# SD_Card.net
KiCad netlist of a schematic drawn in Altium Designer
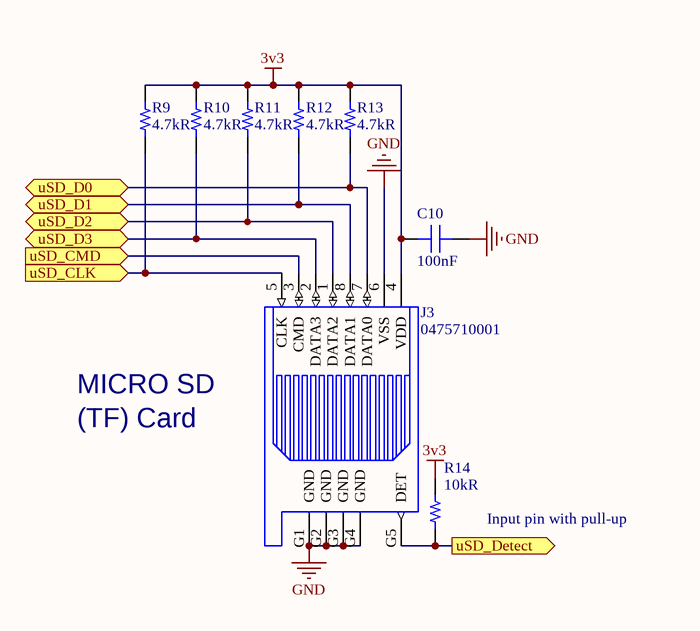
[diagram p0: SD Card.SchDoc]

(export (version "E")
  (design (tool "Eeschema 10.0.6"))
  (components
    (comp (ref "C10")
      (value "100nF")
      (footprint "CAP 0603/1608")
      (description "Ceramic, SMT Capacitor")
      (fields
        (field (name "MANUFACTURER") "Samsung")
        (field (name "MANUFACTURER PART NUMBER") "CL10B104JB8NNNC")
      )
      (libsource (lib "yildizIoT Library") (part "Capacitor - Ceramic"))
    )
    (comp (ref "J3")
      (value "0475710001")
      (footprint "Molex - 0475710001")
      (description "Connector")
      (fields (field (name "MANUFACTURER") "Molex"))
      (libsource (lib "yildizIoT Library") (part "uSD Card"))
    )
    (comp (ref "R9")
      (value "4.7kR")
      (footprint "RES 0603/1608")
      (description "Ceramic, SMT Capacitor")
      (fields
        (field (name "MANUFACTURER") "Yageo")
        (field (name "MANUFACTURER PART NUMBER") "RC0603JR-074K7L")
      )
      (libsource (lib "yildizIoT Library") (part "Resistor_Chip"))
    )
    (comp (ref "R10")
      (value "4.7kR")
      (footprint "RES 0603/1608")
      (description "Ceramic, SMT Capacitor")
      (fields
        (field (name "MANUFACTURER") "Yageo")
        (field (name "MANUFACTURER PART NUMBER") "RC0603JR-074K7L")
      )
      (libsource (lib "yildizIoT Library") (part "Resistor_Chip"))
    )
    (comp (ref "R11")
      (value "4.7kR")
      (footprint "RES 0603/1608")
      (description "Ceramic, SMT Capacitor")
      (fields
        (field (name "MANUFACTURER") "Yageo")
        (field (name "MANUFACTURER PART NUMBER") "RC0603JR-074K7L")
      )
      (libsource (lib "yildizIoT Library") (part "Resistor_Chip"))
    )
    (comp (ref "R12")
      (value "4.7kR")
      (footprint "RES 0603/1608")
      (description "Ceramic, SMT Capacitor")
      (fields
        (field (name "MANUFACTURER") "Yageo")
        (field (name "MANUFACTURER PART NUMBER") "RC0603JR-074K7L")
      )
      (libsource (lib "yildizIoT Library") (part "Resistor_Chip"))
    )
    (comp (ref "R13")
      (value "4.7kR")
      (footprint "RES 0603/1608")
      (description "Ceramic, SMT Capacitor")
      (fields
        (field (name "MANUFACTURER") "Yageo")
        (field (name "MANUFACTURER PART NUMBER") "RC0603JR-074K7L")
      )
      (libsource (lib "yildizIoT Library") (part "Resistor_Chip"))
    )
    (comp (ref "R14")
      (value "10kR")
      (footprint "RES 0603/1608")
      (description "Ceramic, SMT Capacitor")
      (fields
        (field (name "MANUFACTURER") "Stackpole Electronics")
        (field (name "MANUFACTURER PART NUMBER") "RNCP0603FTD10K0")
      )
      (libsource (lib "yildizIoT Library") (part "Resistor_Chip"))
    )
  )
  (nets
    (net (code "1") (name "/uSD_CLK") (class "Default")
      (node (ref "J3") (pin "5") (pinfunction "CLK_5") (pintype "input"))
      (node (ref "R9") (pin "1") (pinfunction "1_1") (pintype "passive"))
    )
    (net (code "2") (name "/uSD_CMD") (class "Default")
      (node (ref "J3") (pin "3") (pinfunction "CMD_3") (pintype "bidirectional"))
    )
    (net (code "3") (name "/uSD_D0") (class "Default")
      (node (ref "J3") (pin "7") (pinfunction "DATA0_7") (pintype "bidirectional"))
      (node (ref "R13") (pin "1") (pinfunction "1_1") (pintype "passive"))
    )
    (net (code "4") (name "/uSD_D1") (class "Default")
      (node (ref "J3") (pin "8") (pinfunction "DATA1_8") (pintype "bidirectional"))
      (node (ref "R12") (pin "1") (pinfunction "1_1") (pintype "passive"))
    )
    (net (code "5") (name "/uSD_D2") (class "Default")
      (node (ref "J3") (pin "1") (pinfunction "DATA2_1") (pintype "bidirectional"))
      (node (ref "R11") (pin "1") (pinfunction "1_1") (pintype "passive"))
    )
    (net (code "6") (name "/uSD_D3") (class "Default")
      (node (ref "J3") (pin "2") (pinfunction "DATA3_2") (pintype "bidirectional"))
      (node (ref "R10") (pin "1") (pinfunction "1_1") (pintype "passive"))
    )
    (net (code "7") (name "/uSD_Detect") (class "Default")
      (node (ref "J3") (pin "G5") (pinfunction "DET_G5") (pintype "output"))
      (node (ref "R14") (pin "1") (pinfunction "1_1") (pintype "passive"))
    )
    (net (code "8") (name "3v3") (class "Default")
      (node (ref "C10") (pin "2") (pinfunction "2_2") (pintype "passive"))
      (node (ref "J3") (pin "4") (pinfunction "VDD_4") (pintype "power_in"))
      (node (ref "R10") (pin "2") (pinfunction "2_2") (pintype "passive"))
      (node (ref "R11") (pin "2") (pinfunction "2_2") (pintype "passive"))
      (node (ref "R12") (pin "2") (pinfunction "2_2") (pintype "passive"))
      (node (ref "R13") (pin "2") (pinfunction "2_2") (pintype "passive"))
      (node (ref "R14") (pin "2") (pinfunction "2_2") (pintype "passive"))
      (node (ref "R9") (pin "2") (pinfunction "2_2") (pintype "passive"))
    )
    (net (code "9") (name "GND") (class "Default")
      (node (ref "C10") (pin "1") (pinfunction "1_1") (pintype "passive"))
      (node (ref "J3") (pin "6") (pinfunction "VSS_6") (pintype "power_in"))
      (node (ref "J3") (pin "G1") (pinfunction "GND_G1") (pintype "power_in"))
      (node (ref "J3") (pin "G2") (pinfunction "GND_G2") (pintype "power_in"))
      (node (ref "J3") (pin "G3") (pinfunction "GND_G3") (pintype "power_in"))
      (node (ref "J3") (pin "G4") (pinfunction "GND_G4") (pintype "power_in"))
    )
  )
)
